# StoneMouse.net
KiCad netlist of a schematic drawn in EAGLE
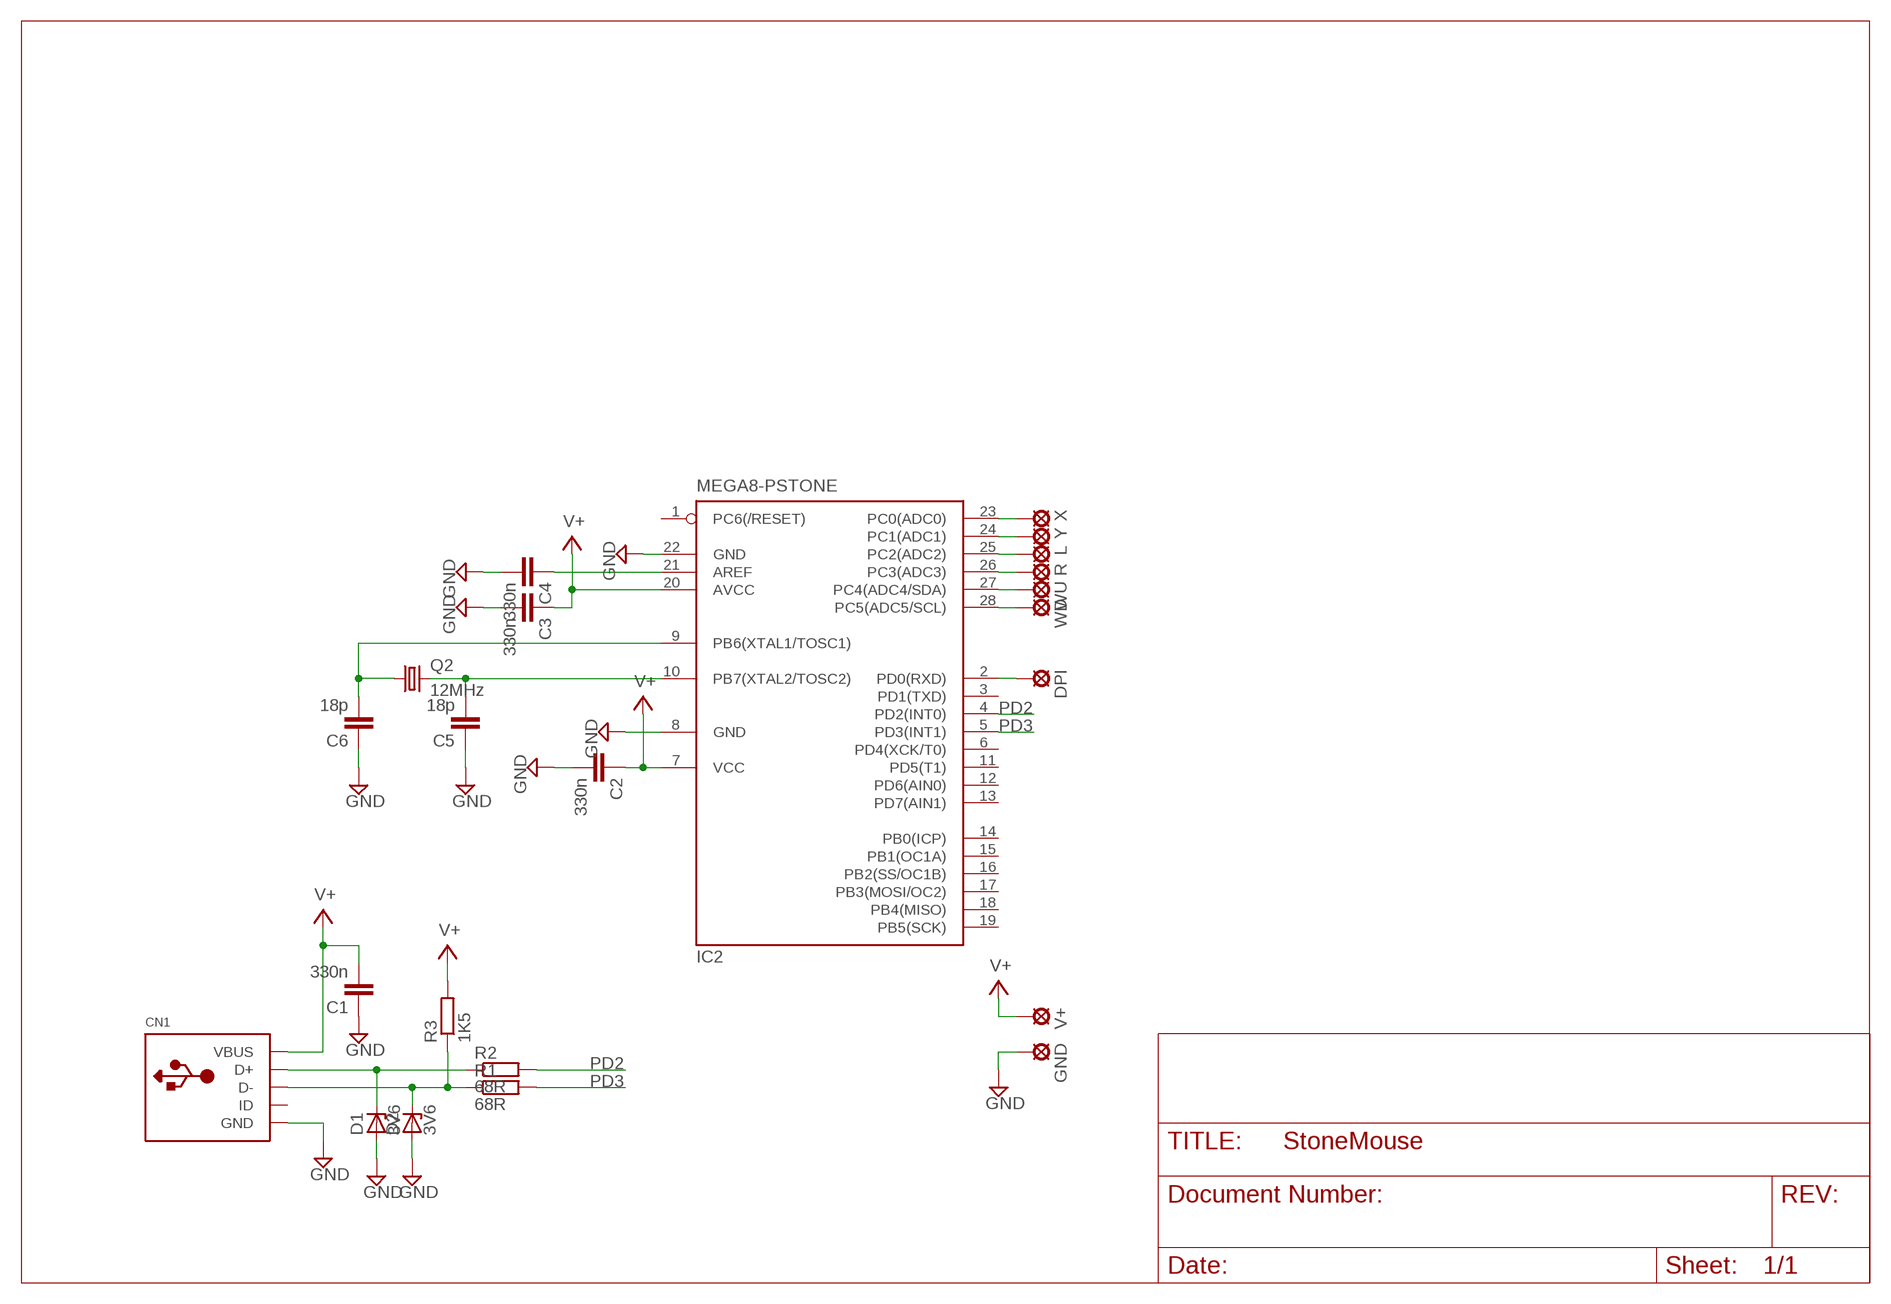
[diagram p0: schematic, sheet 1]

(export (version "E")
  (design (tool "Eeschema 10.0.6"))
  (components
    (comp (ref "C1")
      (value "330n")
      (footprint "eagle-import:3X7_STONESMD")
      (libsource (lib "eagle-import") (part "C-EUSTONESMD"))
    )
    (comp (ref "C2")
      (value "330n")
      (footprint "eagle-import:3X7_STONESMD")
      (libsource (lib "eagle-import") (part "C-EUSTONESMD"))
    )
    (comp (ref "C3")
      (value "330n")
      (footprint "eagle-import:3X7_STONESMD")
      (libsource (lib "eagle-import") (part "C-EUSTONESMD"))
    )
    (comp (ref "C4")
      (value "330n")
      (footprint "eagle-import:3X7_STONESMD")
      (libsource (lib "eagle-import") (part "C-EUSTONESMD"))
    )
    (comp (ref "C5")
      (value "18p")
      (footprint "eagle-import:3X7_STONESMD")
      (libsource (lib "eagle-import") (part "C-EUSTONESMD"))
    )
    (comp (ref "C6")
      (value "18p")
      (footprint "eagle-import:3X7_STONESMD")
      (libsource (lib "eagle-import") (part "C-EUSTONESMD"))
    )
    (comp (ref "CN1")
      (value "USBMINIB")
      (footprint "eagle-import:USB-MINIB")
      (libsource (lib "eagle-import") (part "USBMINIB"))
    )
    (comp (ref "D1")
      (value "3V6")
      (footprint "eagle-import:DO35-7_STONESMD")
      (libsource (lib "eagle-import") (part "BZX85STONESMD"))
    )
    (comp (ref "D2")
      (value "3V6")
      (footprint "eagle-import:DO35-7_STONESMD")
      (libsource (lib "eagle-import") (part "BZX85STONESMD"))
    )
    (comp (ref "DPI")
      (value "SMD3X6")
      (footprint "eagle-import:SMD3X6")
      (libsource (lib "eagle-import") (part "SMD3X6"))
    )
    (comp (ref "GND")
      (value "SMD3X6")
      (footprint "eagle-import:SMD3X6")
      (libsource (lib "eagle-import") (part "SMD3X6"))
    )
    (comp (ref "IC2")
      (value "MEGA8-PSTONE")
      (footprint "eagle-import:DIL28-3_STONESMD")
      (libsource (lib "eagle-import") (part "MEGA8-PSTONE"))
    )
    (comp (ref "L")
      (value "SMD3X6")
      (footprint "eagle-import:SMD3X6")
      (libsource (lib "eagle-import") (part "SMD3X6"))
    )
    (comp (ref "Q2")
      (value "12MHz")
      (footprint "eagle-import:SM49")
      (libsource (lib "eagle-import") (part "CRYSTALSM49"))
    )
    (comp (ref "R")
      (value "SMD3X6")
      (footprint "eagle-import:SMD3X6")
      (libsource (lib "eagle-import") (part "SMD3X6"))
    )
    (comp (ref "R1")
      (value "68R")
      (footprint "eagle-import:0204_7_STONESMD")
      (libsource (lib "eagle-import") (part "R-EU_STONESMD"))
    )
    (comp (ref "R2")
      (value "68R")
      (footprint "eagle-import:0204_7_STONESMD")
      (libsource (lib "eagle-import") (part "R-EU_STONESMD"))
    )
    (comp (ref "R3")
      (value "1K5")
      (footprint "eagle-import:0204_7_STONESMD")
      (libsource (lib "eagle-import") (part "R-EU_STONESMD"))
    )
    (comp (ref "V+")
      (value "SMD3X6")
      (footprint "eagle-import:SMD3X6")
      (libsource (lib "eagle-import") (part "SMD3X6"))
    )
    (comp (ref "WD")
      (value "SMD3X6")
      (footprint "eagle-import:SMD3X6")
      (libsource (lib "eagle-import") (part "SMD3X6"))
    )
    (comp (ref "WU")
      (value "SMD3X6")
      (footprint "eagle-import:SMD3X6")
      (libsource (lib "eagle-import") (part "SMD3X6"))
    )
    (comp (ref "X")
      (value "SMD3X6")
      (footprint "eagle-import:SMD3X6")
      (libsource (lib "eagle-import") (part "SMD3X6"))
    )
    (comp (ref "Y")
      (value "SMD3X6")
      (footprint "eagle-import:SMD3X6")
      (libsource (lib "eagle-import") (part "SMD3X6"))
    )
  )
  (nets
    (net (code "1") (name "/PD2") (class "Default")
      (node (ref "IC2") (pin "4") (pinfunction "PD2(INT0)_4") (pintype "bidirectional"))
      (node (ref "R2") (pin "P$2") (pinfunction "2_P$2") (pintype "passive"))
    )
    (net (code "2") (name "/PD3") (class "Default")
      (node (ref "IC2") (pin "5") (pinfunction "PD3(INT1)_5") (pintype "bidirectional"))
      (node (ref "R1") (pin "P$2") (pinfunction "2_P$2") (pintype "passive"))
    )
    (net (code "3") (name "GND") (class "Default")
      (node (ref "C1") (pin "P$1") (pinfunction "1_P$1") (pintype "passive"))
      (node (ref "C2") (pin "P$2") (pinfunction "2_P$2") (pintype "passive"))
      (node (ref "C3") (pin "P$2") (pinfunction "2_P$2") (pintype "passive"))
      (node (ref "C4") (pin "P$2") (pinfunction "2_P$2") (pintype "passive"))
      (node (ref "C5") (pin "P$1") (pinfunction "1_P$1") (pintype "passive"))
      (node (ref "C6") (pin "P$1") (pinfunction "1_P$1") (pintype "passive"))
      (node (ref "CN1") (pin "GND") (pinfunction "GND_GND") (pintype "power_in"))
      (node (ref "D1") (pin "A") (pinfunction "A_A") (pintype "passive"))
      (node (ref "D2") (pin "A") (pinfunction "A_A") (pintype "passive"))
      (node (ref "GND") (pin "P$1") (pinfunction "MP_P$1") (pintype "passive"))
      (node (ref "IC2") (pin "22") (pinfunction "GND_22") (pintype "power_in"))
      (node (ref "IC2") (pin "8") (pinfunction "GND_8") (pintype "power_in"))
    )
    (net (code "4") (name "Net-(C4-1)") (class "Default")
      (node (ref "C4") (pin "P$1") (pinfunction "1_P$1") (pintype "passive"))
      (node (ref "IC2") (pin "21") (pinfunction "AREF_21") (pintype "passive"))
    )
    (net (code "5") (name "Net-(C5-2)") (class "Default")
      (node (ref "C5") (pin "P$2") (pinfunction "2_P$2") (pintype "passive"))
      (node (ref "IC2") (pin "10") (pinfunction "PB7(XTAL2/TOSC2)_10") (pintype "bidirectional"))
      (node (ref "Q2") (pin "2") (pinfunction "2_2") (pintype "passive"))
    )
    (net (code "6") (name "Net-(C6-2)") (class "Default")
      (node (ref "C6") (pin "P$2") (pinfunction "2_P$2") (pintype "passive"))
      (node (ref "IC2") (pin "9") (pinfunction "PB6(XTAL1/TOSC1)_9") (pintype "bidirectional"))
      (node (ref "Q2") (pin "1") (pinfunction "1_1") (pintype "passive"))
    )
    (net (code "7") (name "Net-(D1-C)") (class "Default")
      (node (ref "CN1") (pin "D+") (pinfunction "D+_D+") (pintype "bidirectional"))
      (node (ref "D1") (pin "K") (pinfunction "C_K") (pintype "passive"))
      (node (ref "R2") (pin "P$1") (pinfunction "1_P$1") (pintype "passive"))
    )
    (net (code "8") (name "Net-(D2-C)") (class "Default")
      (node (ref "CN1") (pin "D-") (pinfunction "D-_D-") (pintype "bidirectional"))
      (node (ref "D2") (pin "K") (pinfunction "C_K") (pintype "passive"))
      (node (ref "R1") (pin "P$1") (pinfunction "1_P$1") (pintype "passive"))
      (node (ref "R3") (pin "P$1") (pinfunction "1_P$1") (pintype "passive"))
    )
    (net (code "9") (name "Net-(DPI-MP)") (class "Default")
      (node (ref "DPI") (pin "P$1") (pinfunction "MP_P$1") (pintype "passive"))
      (node (ref "IC2") (pin "2") (pinfunction "PD0(RXD)_2") (pintype "bidirectional"))
    )
    (net (code "10") (name "Net-(IC2-PC0(ADC0))") (class "Default")
      (node (ref "IC2") (pin "23") (pinfunction "PC0(ADC0)_23") (pintype "bidirectional"))
      (node (ref "X") (pin "P$1") (pinfunction "MP_P$1") (pintype "passive"))
    )
    (net (code "11") (name "Net-(IC2-PC1(ADC1))") (class "Default")
      (node (ref "IC2") (pin "24") (pinfunction "PC1(ADC1)_24") (pintype "bidirectional"))
      (node (ref "Y") (pin "P$1") (pinfunction "MP_P$1") (pintype "passive"))
    )
    (net (code "12") (name "Net-(IC2-PC2(ADC2))") (class "Default")
      (node (ref "IC2") (pin "25") (pinfunction "PC2(ADC2)_25") (pintype "bidirectional"))
      (node (ref "L") (pin "P$1") (pinfunction "MP_P$1") (pintype "passive"))
    )
    (net (code "13") (name "Net-(IC2-PC3(ADC3))") (class "Default")
      (node (ref "IC2") (pin "26") (pinfunction "PC3(ADC3)_26") (pintype "bidirectional"))
      (node (ref "R") (pin "P$1") (pinfunction "MP_P$1") (pintype "passive"))
    )
    (net (code "14") (name "Net-(IC2-PC4(ADC4{slash}SDA))") (class "Default")
      (node (ref "IC2") (pin "27") (pinfunction "PC4(ADC4/SDA)_27") (pintype "bidirectional"))
      (node (ref "WU") (pin "P$1") (pinfunction "MP_P$1") (pintype "passive"))
    )
    (net (code "15") (name "Net-(IC2-PC5(ADC5{slash}SCL))") (class "Default")
      (node (ref "IC2") (pin "28") (pinfunction "PC5(ADC5/SCL)_28") (pintype "bidirectional"))
      (node (ref "WD") (pin "P$1") (pinfunction "MP_P$1") (pintype "passive"))
    )
    (net (code "16") (name "V+") (class "Default")
      (node (ref "C1") (pin "P$2") (pinfunction "2_P$2") (pintype "passive"))
      (node (ref "C2") (pin "P$1") (pinfunction "1_P$1") (pintype "passive"))
      (node (ref "C3") (pin "P$1") (pinfunction "1_P$1") (pintype "passive"))
      (node (ref "CN1") (pin "VBUS") (pinfunction "VBUS_VBUS") (pintype "power_in"))
      (node (ref "IC2") (pin "20") (pinfunction "AVCC_20") (pintype "power_in"))
      (node (ref "IC2") (pin "7") (pinfunction "VCC_7") (pintype "power_in"))
      (node (ref "R3") (pin "P$2") (pinfunction "2_P$2") (pintype "passive"))
      (node (ref "V+") (pin "P$1") (pinfunction "MP_P$1") (pintype "passive"))
    )
    (net (code "17") (name "unconnected-(CN1-PadID)") (class "Default")
      (node (ref "CN1") (pin "ID") (pinfunction "ID_ID") (pintype "bidirectional"))
    )
    (net (code "18") (name "unconnected-(IC2-PB0(ICP)-Pad14)") (class "Default")
      (node (ref "IC2") (pin "14") (pinfunction "PB0(ICP)_14") (pintype "bidirectional"))
    )
    (net (code "19") (name "unconnected-(IC2-PB1(OC1A)-Pad15)") (class "Default")
      (node (ref "IC2") (pin "15") (pinfunction "PB1(OC1A)_15") (pintype "bidirectional"))
    )
    (net (code "20") (name "unconnected-(IC2-PB2(SS{slash}OC1B)-Pad16)") (class "Default")
      (node (ref "IC2") (pin "16") (pinfunction "PB2(SS/OC1B)_16") (pintype "bidirectional"))
    )
    (net (code "21") (name "unconnected-(IC2-PB3(MOSI{slash}OC2)-Pad17)") (class "Default")
      (node (ref "IC2") (pin "17") (pinfunction "PB3(MOSI/OC2)_17") (pintype "bidirectional"))
    )
    (net (code "22") (name "unconnected-(IC2-PB4(MISO)-Pad18)") (class "Default")
      (node (ref "IC2") (pin "18") (pinfunction "PB4(MISO)_18") (pintype "bidirectional"))
    )
    (net (code "23") (name "unconnected-(IC2-PB5(SCK)-Pad19)") (class "Default")
      (node (ref "IC2") (pin "19") (pinfunction "PB5(SCK)_19") (pintype "bidirectional"))
    )
    (net (code "24") (name "unconnected-(IC2-PC6({slash}RESET)-Pad1)") (class "Default")
      (node (ref "IC2") (pin "1") (pinfunction "PC6(/RESET)_1") (pintype "bidirectional"))
    )
    (net (code "25") (name "unconnected-(IC2-PD1(TXD)-Pad3)") (class "Default")
      (node (ref "IC2") (pin "3") (pinfunction "PD1(TXD)_3") (pintype "bidirectional"))
    )
    (net (code "26") (name "unconnected-(IC2-PD4(XCK{slash}T0)-Pad6)") (class "Default")
      (node (ref "IC2") (pin "6") (pinfunction "PD4(XCK/T0)_6") (pintype "bidirectional"))
    )
    (net (code "27") (name "unconnected-(IC2-PD5(T1)-Pad11)") (class "Default")
      (node (ref "IC2") (pin "11") (pinfunction "PD5(T1)_11") (pintype "bidirectional"))
    )
    (net (code "28") (name "unconnected-(IC2-PD6(AIN0)-Pad12)") (class "Default")
      (node (ref "IC2") (pin "12") (pinfunction "PD6(AIN0)_12") (pintype "bidirectional"))
    )
    (net (code "29") (name "unconnected-(IC2-PD7(AIN1)-Pad13)") (class "Default")
      (node (ref "IC2") (pin "13") (pinfunction "PD7(AIN1)_13") (pintype "bidirectional"))
    )
  )
)
